# BC35_module.net
KiCad netlist of a schematic drawn in Altium Designer
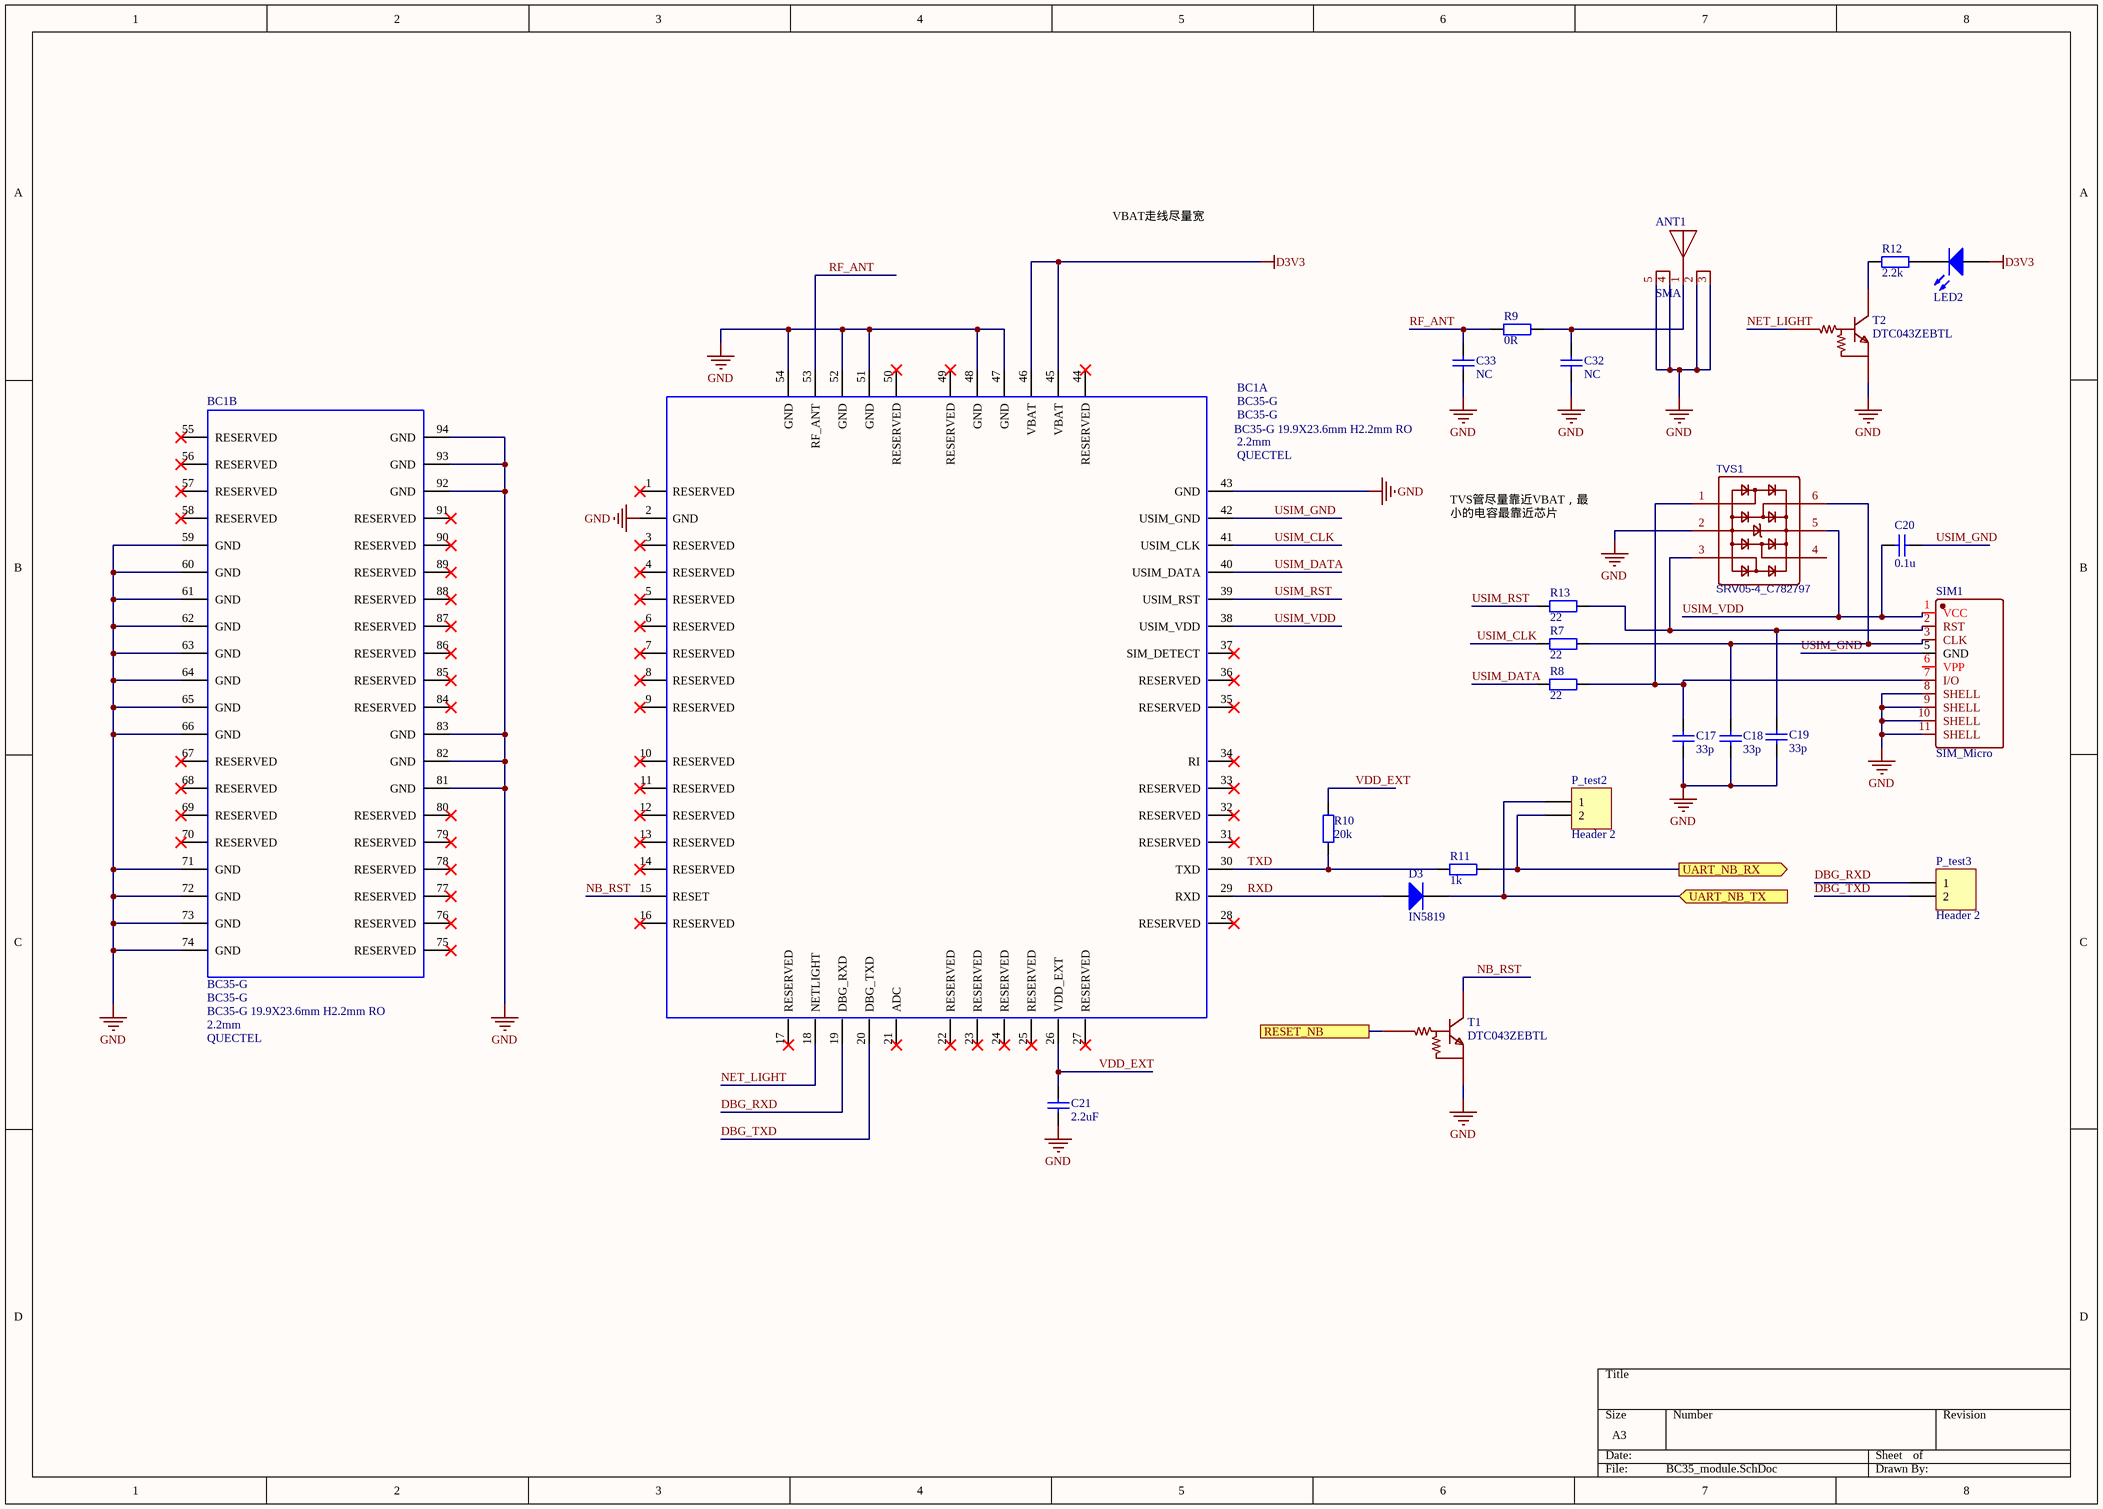
[diagram p0: BC35_module.SchDoc]

(export (version "E")
  (design (tool "Eeschema 10.0.6"))
  (components
    (comp (ref "ANT1")
      (value "SMA")
      (footprint "ANT-TH_DOSIN-806-0003")
      (libsource (lib "NBIoT") (part "SMA"))
    )
    (comp (ref "BC1")
      (value "BC35-G")
      (footprint "Quectel_BC35-G_PCB_Footprint_Protel&AD_20171010:BC35-G")
      (fields
        (field (name "ALTIUM_VALUE") "BC35-G")
        (field (name "PART DESCRIPTION") "BC35-G 19.9X23.6mm H2.2mm RO")
        (field (name "GEOMETRY.HEIGHT") "2.2mm")
        (field (name "MANUFACTURER") "QUECTEL")
      )
      (libsource (lib "Quectel_BC35-G_SCH_Part_Protel&AD_20171010") (part "BC35-G"))
    )
    (comp (ref "C17")
      (value "33p")
      (footprint "1206_C")
      (description "1206贴片电容")
      (libsource (lib "02-Miscellaneous_Devices_ZSF_Library") (part "Cap_1206"))
    )
    (comp (ref "C18")
      (value "33p")
      (footprint "1206_C")
      (description "1206贴片电容")
      (libsource (lib "02-Miscellaneous_Devices_ZSF_Library") (part "Cap_1206"))
    )
    (comp (ref "C19")
      (value "33p")
      (footprint "1206_C")
      (description "1206贴片电容")
      (libsource (lib "02-Miscellaneous_Devices_ZSF_Library") (part "Cap_1206"))
    )
    (comp (ref "C20")
      (value "0.1u")
      (footprint "1206_C")
      (description "1206贴片电容")
      (libsource (lib "02-Miscellaneous_Devices_ZSF_Library") (part "Cap_1206"))
    )
    (comp (ref "C21")
      (value "2.2uF")
      (footprint "1206_C")
      (description "1206贴片电容")
      (libsource (lib "02-Miscellaneous_Devices_ZSF_Library") (part "Cap_1206"))
    )
    (comp (ref "C32")
      (value "NC")
      (footprint "1206_C")
      (description "1206贴片电容")
      (libsource (lib "02-Miscellaneous_Devices_ZSF_Library") (part "Cap_1206"))
    )
    (comp (ref "C33")
      (value "NC")
      (footprint "1206_C")
      (description "1206贴片电容")
      (libsource (lib "02-Miscellaneous_Devices_ZSF_Library") (part "Cap_1206"))
    )
    (comp (ref "D3")
      (value "IN5819")
      (footprint "SOD-323")
      (description "二极管")
      (libsource (lib "02-Miscellaneous_Devices_ZSF_Library") (part "1N4148WS_SOD-323"))
    )
    (comp (ref "LED2")
      (value "LED Chip")
      (footprint "CLED2012-0805")
      (description "Typical Chip LED")
      (fields (field (name "PUBLISHER") "Altium Limited"))
      (libsource (lib "03-EButterflyIntegratedLibrary") (part "LED Chip"))
    )
    (comp (ref "P_test2")
      (value "Header 2")
      (footprint "XH254-2")
      (description "Header, 2-Pin")
      (fields (field (name "PUBLISHER") "Altium Limited"))
      (libsource (lib "01-Connect_IntegratedLibrary") (part "Header 2"))
    )
    (comp (ref "P_test3")
      (value "Header 2")
      (footprint "XH254-2")
      (description "Header, 2-Pin")
      (fields (field (name "PUBLISHER") "Altium Limited"))
      (libsource (lib "01-Connect_IntegratedLibrary") (part "Header 2"))
    )
    (comp (ref "R7")
      (value "22")
      (footprint "0805_R")
      (description "0805贴片电阻")
      (libsource (lib "02-Miscellaneous_Devices_ZSF_Library") (part "Res_0805"))
    )
    (comp (ref "R8")
      (value "22")
      (footprint "0805_R")
      (description "0805贴片电阻")
      (libsource (lib "02-Miscellaneous_Devices_ZSF_Library") (part "Res_0805"))
    )
    (comp (ref "R9")
      (value "0R")
      (footprint "0805_R")
      (description "0805贴片电阻")
      (libsource (lib "02-Miscellaneous_Devices_ZSF_Library") (part "Res_0805"))
    )
    (comp (ref "R10")
      (value "20k")
      (footprint "0805_R")
      (description "0805贴片电阻")
      (libsource (lib "") (part "Res_0805_1"))
    )
    (comp (ref "R11")
      (value "1k")
      (footprint "0805_R")
      (description "0805贴片电阻")
      (libsource (lib "02-Miscellaneous_Devices_ZSF_Library") (part "Res_0805"))
    )
    (comp (ref "R12")
      (value "2.2k")
      (footprint "0805_R")
      (description "0805贴片电阻")
      (libsource (lib "02-Miscellaneous_Devices_ZSF_Library") (part "Res_0805"))
    )
    (comp (ref "R13")
      (value "22")
      (footprint "0805_R")
      (description "0805贴片电阻")
      (libsource (lib "02-Miscellaneous_Devices_ZSF_Library") (part "Res_0805"))
    )
    (comp (ref "SIM1")
      (value "SIM_Micro")
      (footprint "SIM-SMD_SIM-002-P6")
      (libsource (lib "NBIoT") (part "SIM_Micro"))
    )
    (comp (ref "T1")
      (value "DTC043ZEBTL")
      (footprint "SOT-416_L1.6-W0.8-P1.00-LS1.6-BR")
      (libsource (lib "NBIoT") (part "DTC043ZEBTL"))
    )
    (comp (ref "T2")
      (value "DTC043ZEBTL")
      (footprint "SOT-416_L1.6-W0.8-P1.00-LS1.6-BR")
      (libsource (lib "NBIoT") (part "DTC043ZEBTL"))
    )
    (comp (ref "TVS1")
      (value "SRV05-4_C782797")
      (footprint "SOT-23-6_L2.9-W1.6-P0.95-LS2.8-BR")
      (fields
        (field (name "BOM_SUPPLIER PART") "C782797")
        (field (name "BOM_MANUFACTURER PART") "SRV05-4")
        (field (name "CONTRIBUTOR") "LCSC")
      )
      (libsource (lib "NBIoT") (part "SRV05-4_C782797"))
    )
  )
  (nets
    (net (code "1") (name "/DBG_RXD") (class "Default")
      (node (ref "BC1") (pin "19") (pinfunction "DBG_RXD_19") (pintype "passive"))
      (node (ref "P_test3") (pin "1") (pinfunction "1_1") (pintype "passive"))
    )
    (net (code "2") (name "/DBG_TXD") (class "Default")
      (node (ref "BC1") (pin "20") (pinfunction "DBG_TXD_20") (pintype "passive"))
      (node (ref "P_test3") (pin "2") (pinfunction "2_2") (pintype "passive"))
    )
    (net (code "3") (name "/NB_RST") (class "Default")
      (node (ref "BC1") (pin "15") (pinfunction "RESET_15") (pintype "passive"))
      (node (ref "T1") (pin "3") (pinfunction "C_3") (pintype "passive"))
    )
    (net (code "4") (name "/NET_LIGHT") (class "Default")
      (node (ref "BC1") (pin "18") (pinfunction "NETLIGHT_18") (pintype "passive"))
      (node (ref "T2") (pin "1") (pinfunction "B_1") (pintype "passive"))
    )
    (net (code "5") (name "/RESET_NB") (class "Default")
      (node (ref "T1") (pin "1") (pinfunction "B_1") (pintype "passive"))
    )
    (net (code "6") (name "/RF_ANT") (class "Default")
      (node (ref "BC1") (pin "53") (pinfunction "RF_ANT_53") (pintype "passive"))
      (node (ref "C33") (pin "2") (pinfunction "2_2") (pintype "passive"))
      (node (ref "R9") (pin "2") (pinfunction "2_2") (pintype "passive"))
    )
    (net (code "7") (name "/RXD") (class "Default")
      (node (ref "BC1") (pin "29") (pinfunction "RXD_29") (pintype "passive"))
      (node (ref "D3") (pin "1") (pinfunction "A_1") (pintype "passive"))
    )
    (net (code "8") (name "/TXD") (class "Default")
      (node (ref "BC1") (pin "30") (pinfunction "TXD_30") (pintype "passive"))
      (node (ref "R10") (pin "2") (pinfunction "2_2") (pintype "passive"))
      (node (ref "R11") (pin "2") (pinfunction "2_2") (pintype "passive"))
    )
    (net (code "9") (name "/UART_NB_RX") (class "Default")
      (node (ref "P_test2") (pin "2") (pinfunction "2_2") (pintype "passive"))
      (node (ref "R11") (pin "1") (pinfunction "1_1") (pintype "passive"))
    )
    (net (code "10") (name "/UART_NB_TX") (class "Default")
      (node (ref "D3") (pin "2") (pinfunction "K_2") (pintype "passive"))
      (node (ref "P_test2") (pin "1") (pinfunction "1_1") (pintype "passive"))
    )
    (net (code "11") (name "/USIM_CLK") (class "Default")
      (node (ref "BC1") (pin "41") (pinfunction "USIM_CLK_41") (pintype "passive"))
      (node (ref "R7") (pin "2") (pinfunction "2_2") (pintype "passive"))
    )
    (net (code "12") (name "/USIM_DATA") (class "Default")
      (node (ref "BC1") (pin "40") (pinfunction "USIM_DATA_40") (pintype "passive"))
      (node (ref "R8") (pin "2") (pinfunction "2_2") (pintype "passive"))
    )
    (net (code "13") (name "/USIM_GND") (class "Default")
      (node (ref "BC1") (pin "42") (pinfunction "USIM_GND_42") (pintype "passive"))
      (node (ref "C20") (pin "1") (pinfunction "1_1") (pintype "passive"))
      (node (ref "SIM1") (pin "5") (pinfunction "GND_5") (pintype "passive"))
    )
    (net (code "14") (name "/USIM_RST") (class "Default")
      (node (ref "BC1") (pin "39") (pinfunction "USIM_RST_39") (pintype "passive"))
      (node (ref "R13") (pin "2") (pinfunction "2_2") (pintype "passive"))
    )
    (net (code "15") (name "/USIM_VDD") (class "Default")
      (node (ref "BC1") (pin "38") (pinfunction "USIM_VDD_38") (pintype "passive"))
      (node (ref "C20") (pin "2") (pinfunction "2_2") (pintype "passive"))
      (node (ref "SIM1") (pin "1") (pinfunction "VCC_1") (pintype "passive"))
      (node (ref "TVS1") (pin "5") (pinfunction "5_5") (pintype "passive"))
    )
    (net (code "16") (name "/VDD_EXT") (class "Default")
      (node (ref "BC1") (pin "26") (pinfunction "VDD_EXT_26") (pintype "passive"))
      (node (ref "C21") (pin "2") (pinfunction "2_2") (pintype "passive"))
      (node (ref "R10") (pin "1") (pinfunction "1_1") (pintype "passive"))
    )
    (net (code "17") (name "D3V3") (class "Default")
      (node (ref "BC1") (pin "45") (pinfunction "VBAT_45") (pintype "passive"))
      (node (ref "BC1") (pin "46") (pinfunction "VBAT_46") (pintype "passive"))
      (node (ref "LED2") (pin "1") (pinfunction "A_1") (pintype "passive"))
    )
    (net (code "18") (name "GND") (class "Default")
      (node (ref "ANT1") (pin "2") (pinfunction "2_2") (pintype "passive"))
      (node (ref "ANT1") (pin "3") (pinfunction "3_3") (pintype "passive"))
      (node (ref "ANT1") (pin "4") (pinfunction "4_4") (pintype "passive"))
      (node (ref "ANT1") (pin "5") (pinfunction "5_5") (pintype "passive"))
      (node (ref "BC1") (pin "2") (pinfunction "GND_2") (pintype "passive"))
      (node (ref "BC1") (pin "43") (pinfunction "GND_43") (pintype "passive"))
      (node (ref "BC1") (pin "47") (pinfunction "GND_47") (pintype "passive"))
      (node (ref "BC1") (pin "48") (pinfunction "GND_48") (pintype "passive"))
      (node (ref "BC1") (pin "51") (pinfunction "GND_51") (pintype "passive"))
      (node (ref "BC1") (pin "52") (pinfunction "GND_52") (pintype "passive"))
      (node (ref "BC1") (pin "54") (pinfunction "GND_54") (pintype "passive"))
      (node (ref "BC1") (pin "59") (pinfunction "GND_59") (pintype "passive"))
      (node (ref "BC1") (pin "60") (pinfunction "GND_60") (pintype "passive"))
      (node (ref "BC1") (pin "61") (pinfunction "GND_61") (pintype "passive"))
      (node (ref "BC1") (pin "62") (pinfunction "GND_62") (pintype "passive"))
      (node (ref "BC1") (pin "63") (pinfunction "GND_63") (pintype "passive"))
      (node (ref "BC1") (pin "64") (pinfunction "GND_64") (pintype "passive"))
      (node (ref "BC1") (pin "65") (pinfunction "GND_65") (pintype "passive"))
      (node (ref "BC1") (pin "66") (pinfunction "GND_66") (pintype "passive"))
      (node (ref "BC1") (pin "71") (pinfunction "GND_71") (pintype "passive"))
      (node (ref "BC1") (pin "72") (pinfunction "GND_72") (pintype "passive"))
      (node (ref "BC1") (pin "73") (pinfunction "GND_73") (pintype "passive"))
      (node (ref "BC1") (pin "74") (pinfunction "GND_74") (pintype "passive"))
      (node (ref "BC1") (pin "81") (pinfunction "GND_81") (pintype "passive"))
      (node (ref "BC1") (pin "82") (pinfunction "GND_82") (pintype "passive"))
      (node (ref "BC1") (pin "83") (pinfunction "GND_83") (pintype "passive"))
      (node (ref "BC1") (pin "92") (pinfunction "GND_92") (pintype "passive"))
      (node (ref "BC1") (pin "93") (pinfunction "GND_93") (pintype "passive"))
      (node (ref "BC1") (pin "94") (pinfunction "GND_94") (pintype "passive"))
      (node (ref "C17") (pin "1") (pinfunction "1_1") (pintype "passive"))
      (node (ref "C18") (pin "1") (pinfunction "1_1") (pintype "passive"))
      (node (ref "C19") (pin "1") (pinfunction "1_1") (pintype "passive"))
      (node (ref "C21") (pin "1") (pinfunction "1_1") (pintype "passive"))
      (node (ref "C32") (pin "1") (pinfunction "1_1") (pintype "passive"))
      (node (ref "C33") (pin "1") (pinfunction "1_1") (pintype "passive"))
      (node (ref "SIM1") (pin "10") (pinfunction "SHELL_10") (pintype "passive"))
      (node (ref "SIM1") (pin "11") (pinfunction "SHELL_11") (pintype "passive"))
      (node (ref "SIM1") (pin "8") (pinfunction "SHELL_8") (pintype "passive"))
      (node (ref "SIM1") (pin "9") (pinfunction "SHELL_9") (pintype "passive"))
      (node (ref "T1") (pin "2") (pinfunction "E_2") (pintype "passive"))
      (node (ref "T2") (pin "2") (pinfunction "E_2") (pintype "passive"))
      (node (ref "TVS1") (pin "2") (pinfunction "2_2") (pintype "passive"))
    )
    (net (code "19") (name "Net-(ANT1-Pad1)") (class "Default")
      (node (ref "ANT1") (pin "1") (pinfunction "1_1") (pintype "passive"))
      (node (ref "C32") (pin "2") (pinfunction "2_2") (pintype "passive"))
      (node (ref "R9") (pin "1") (pinfunction "1_1") (pintype "passive"))
    )
    (net (code "20") (name "Net-(LED2-K)") (class "Default")
      (node (ref "LED2") (pin "2") (pinfunction "K_2") (pintype "passive"))
      (node (ref "R12") (pin "1") (pinfunction "1_1") (pintype "passive"))
    )
    (net (code "21") (name "Net-(SIM1-CLK)") (class "Default")
      (node (ref "C18") (pin "2") (pinfunction "2_2") (pintype "passive"))
      (node (ref "R7") (pin "1") (pinfunction "1_1") (pintype "passive"))
      (node (ref "SIM1") (pin "3") (pinfunction "CLK_3") (pintype "passive"))
      (node (ref "TVS1") (pin "6") (pinfunction "6_6") (pintype "passive"))
    )
    (net (code "22") (name "Net-(SIM1-I{slash}O)") (class "Default")
      (node (ref "C17") (pin "2") (pinfunction "2_2") (pintype "passive"))
      (node (ref "R8") (pin "1") (pinfunction "1_1") (pintype "passive"))
      (node (ref "SIM1") (pin "7") (pinfunction "I/O_7") (pintype "passive"))
      (node (ref "TVS1") (pin "1") (pinfunction "1_1") (pintype "passive"))
    )
    (net (code "23") (name "Net-(SIM1-RST)") (class "Default")
      (node (ref "C19") (pin "2") (pinfunction "2_2") (pintype "passive"))
      (node (ref "R13") (pin "1") (pinfunction "1_1") (pintype "passive"))
      (node (ref "SIM1") (pin "2") (pinfunction "RST_2") (pintype "passive"))
      (node (ref "TVS1") (pin "3") (pinfunction "3_3") (pintype "passive"))
    )
    (net (code "24") (name "Net-(T2-C)") (class "Default")
      (node (ref "R12") (pin "2") (pinfunction "2_2") (pintype "passive"))
      (node (ref "T2") (pin "3") (pinfunction "C_3") (pintype "passive"))
    )
    (net (code "25") (name "unconnected-(BC1A-ADC-Pad21)") (class "Default")
      (node (ref "BC1") (pin "21") (pinfunction "ADC_21") (pintype "passive+no_connect"))
    )
    (net (code "26") (name "unconnected-(BC1A-RESERVED-Pad1)") (class "Default")
      (node (ref "BC1") (pin "1") (pinfunction "RESERVED_1") (pintype "passive+no_connect"))
    )
    (net (code "27") (name "unconnected-(BC1A-RESERVED-Pad3)") (class "Default")
      (node (ref "BC1") (pin "3") (pinfunction "RESERVED_3") (pintype "passive+no_connect"))
    )
    (net (code "28") (name "unconnected-(BC1A-RESERVED-Pad4)") (class "Default")
      (node (ref "BC1") (pin "4") (pinfunction "RESERVED_4") (pintype "passive+no_connect"))
    )
    (net (code "29") (name "unconnected-(BC1A-RESERVED-Pad5)") (class "Default")
      (node (ref "BC1") (pin "5") (pinfunction "RESERVED_5") (pintype "passive+no_connect"))
    )
    (net (code "30") (name "unconnected-(BC1A-RESERVED-Pad6)") (class "Default")
      (node (ref "BC1") (pin "6") (pinfunction "RESERVED_6") (pintype "passive+no_connect"))
    )
    (net (code "31") (name "unconnected-(BC1A-RESERVED-Pad7)") (class "Default")
      (node (ref "BC1") (pin "7") (pinfunction "RESERVED_7") (pintype "passive+no_connect"))
    )
    (net (code "32") (name "unconnected-(BC1A-RESERVED-Pad8)") (class "Default")
      (node (ref "BC1") (pin "8") (pinfunction "RESERVED_8") (pintype "passive+no_connect"))
    )
    (net (code "33") (name "unconnected-(BC1A-RESERVED-Pad9)") (class "Default")
      (node (ref "BC1") (pin "9") (pinfunction "RESERVED_9") (pintype "passive+no_connect"))
    )
    (net (code "34") (name "unconnected-(BC1A-RESERVED-Pad10)") (class "Default")
      (node (ref "BC1") (pin "10") (pinfunction "RESERVED_10") (pintype "passive+no_connect"))
    )
    (net (code "35") (name "unconnected-(BC1A-RESERVED-Pad11)") (class "Default")
      (node (ref "BC1") (pin "11") (pinfunction "RESERVED_11") (pintype "passive+no_connect"))
    )
    (net (code "36") (name "unconnected-(BC1A-RESERVED-Pad12)") (class "Default")
      (node (ref "BC1") (pin "12") (pinfunction "RESERVED_12") (pintype "passive+no_connect"))
    )
    (net (code "37") (name "unconnected-(BC1A-RESERVED-Pad13)") (class "Default")
      (node (ref "BC1") (pin "13") (pinfunction "RESERVED_13") (pintype "passive+no_connect"))
    )
    (net (code "38") (name "unconnected-(BC1A-RESERVED-Pad14)") (class "Default")
      (node (ref "BC1") (pin "14") (pinfunction "RESERVED_14") (pintype "passive+no_connect"))
    )
    (net (code "39") (name "unconnected-(BC1A-RESERVED-Pad16)") (class "Default")
      (node (ref "BC1") (pin "16") (pinfunction "RESERVED_16") (pintype "passive+no_connect"))
    )
    (net (code "40") (name "unconnected-(BC1A-RESERVED-Pad17)") (class "Default")
      (node (ref "BC1") (pin "17") (pinfunction "RESERVED_17") (pintype "passive+no_connect"))
    )
    (net (code "41") (name "unconnected-(BC1A-RESERVED-Pad22)") (class "Default")
      (node (ref "BC1") (pin "22") (pinfunction "RESERVED_22") (pintype "passive+no_connect"))
    )
    (net (code "42") (name "unconnected-(BC1A-RESERVED-Pad23)") (class "Default")
      (node (ref "BC1") (pin "23") (pinfunction "RESERVED_23") (pintype "passive+no_connect"))
    )
    (net (code "43") (name "unconnected-(BC1A-RESERVED-Pad24)") (class "Default")
      (node (ref "BC1") (pin "24") (pinfunction "RESERVED_24") (pintype "passive+no_connect"))
    )
    (net (code "44") (name "unconnected-(BC1A-RESERVED-Pad25)") (class "Default")
      (node (ref "BC1") (pin "25") (pinfunction "RESERVED_25") (pintype "passive+no_connect"))
    )
    (net (code "45") (name "unconnected-(BC1A-RESERVED-Pad27)") (class "Default")
      (node (ref "BC1") (pin "27") (pinfunction "RESERVED_27") (pintype "passive+no_connect"))
    )
    (net (code "46") (name "unconnected-(BC1A-RESERVED-Pad28)") (class "Default")
      (node (ref "BC1") (pin "28") (pinfunction "RESERVED_28") (pintype "passive+no_connect"))
    )
    (net (code "47") (name "unconnected-(BC1A-RESERVED-Pad31)") (class "Default")
      (node (ref "BC1") (pin "31") (pinfunction "RESERVED_31") (pintype "passive+no_connect"))
    )
    (net (code "48") (name "unconnected-(BC1A-RESERVED-Pad32)") (class "Default")
      (node (ref "BC1") (pin "32") (pinfunction "RESERVED_32") (pintype "passive+no_connect"))
    )
    (net (code "49") (name "unconnected-(BC1A-RESERVED-Pad33)") (class "Default")
      (node (ref "BC1") (pin "33") (pinfunction "RESERVED_33") (pintype "passive+no_connect"))
    )
    (net (code "50") (name "unconnected-(BC1A-RESERVED-Pad35)") (class "Default")
      (node (ref "BC1") (pin "35") (pinfunction "RESERVED_35") (pintype "passive+no_connect"))
    )
    (net (code "51") (name "unconnected-(BC1A-RESERVED-Pad36)") (class "Default")
      (node (ref "BC1") (pin "36") (pinfunction "RESERVED_36") (pintype "passive+no_connect"))
    )
    (net (code "52") (name "unconnected-(BC1A-RESERVED-Pad44)") (class "Default")
      (node (ref "BC1") (pin "44") (pinfunction "RESERVED_44") (pintype "passive+no_connect"))
    )
    (net (code "53") (name "unconnected-(BC1A-RESERVED-Pad49)") (class "Default")
      (node (ref "BC1") (pin "49") (pinfunction "RESERVED_49") (pintype "passive+no_connect"))
    )
    (net (code "54") (name "unconnected-(BC1A-RESERVED-Pad50)") (class "Default")
      (node (ref "BC1") (pin "50") (pinfunction "RESERVED_50") (pintype "passive+no_connect"))
    )
    (net (code "55") (name "unconnected-(BC1A-RI-Pad34)") (class "Default")
      (node (ref "BC1") (pin "34") (pinfunction "RI_34") (pintype "passive+no_connect"))
    )
    (net (code "56") (name "unconnected-(BC1A-SIM_DETECT-Pad37)") (class "Default")
      (node (ref "BC1") (pin "37") (pinfunction "SIM_DETECT_37") (pintype "passive+no_connect"))
    )
    (net (code "57") (name "unconnected-(BC1B-RESERVED-Pad55)") (class "Default")
      (node (ref "BC1") (pin "55") (pinfunction "RESERVED_55") (pintype "passive+no_connect"))
    )
    (net (code "58") (name "unconnected-(BC1B-RESERVED-Pad56)") (class "Default")
      (node (ref "BC1") (pin "56") (pinfunction "RESERVED_56") (pintype "passive+no_connect"))
    )
    (net (code "59") (name "unconnected-(BC1B-RESERVED-Pad57)") (class "Default")
      (node (ref "BC1") (pin "57") (pinfunction "RESERVED_57") (pintype "passive+no_connect"))
    )
    (net (code "60") (name "unconnected-(BC1B-RESERVED-Pad58)") (class "Default")
      (node (ref "BC1") (pin "58") (pinfunction "RESERVED_58") (pintype "passive+no_connect"))
    )
    (net (code "61") (name "unconnected-(BC1B-RESERVED-Pad67)") (class "Default")
      (node (ref "BC1") (pin "67") (pinfunction "RESERVED_67") (pintype "passive+no_connect"))
    )
    (net (code "62") (name "unconnected-(BC1B-RESERVED-Pad68)") (class "Default")
      (node (ref "BC1") (pin "68") (pinfunction "RESERVED_68") (pintype "passive+no_connect"))
    )
    (net (code "63") (name "unconnected-(BC1B-RESERVED-Pad69)") (class "Default")
      (node (ref "BC1") (pin "69") (pinfunction "RESERVED_69") (pintype "passive+no_connect"))
    )
    (net (code "64") (name "unconnected-(BC1B-RESERVED-Pad70)") (class "Default")
      (node (ref "BC1") (pin "70") (pinfunction "RESERVED_70") (pintype "passive+no_connect"))
    )
    (net (code "65") (name "unconnected-(BC1B-RESERVED-Pad75)") (class "Default")
      (node (ref "BC1") (pin "75") (pinfunction "RESERVED_75") (pintype "passive+no_connect"))
    )
    (net (code "66") (name "unconnected-(BC1B-RESERVED-Pad76)") (class "Default")
      (node (ref "BC1") (pin "76") (pinfunction "RESERVED_76") (pintype "passive+no_connect"))
    )
    (net (code "67") (name "unconnected-(BC1B-RESERVED-Pad77)") (class "Default")
      (node (ref "BC1") (pin "77") (pinfunction "RESERVED_77") (pintype "passive+no_connect"))
    )
    (net (code "68") (name "unconnected-(BC1B-RESERVED-Pad78)") (class "Default")
      (node (ref "BC1") (pin "78") (pinfunction "RESERVED_78") (pintype "passive+no_connect"))
    )
    (net (code "69") (name "unconnected-(BC1B-RESERVED-Pad79)") (class "Default")
      (node (ref "BC1") (pin "79") (pinfunction "RESERVED_79") (pintype "passive+no_connect"))
    )
    (net (code "70") (name "unconnected-(BC1B-RESERVED-Pad80)") (class "Default")
      (node (ref "BC1") (pin "80") (pinfunction "RESERVED_80") (pintype "passive+no_connect"))
    )
    (net (code "71") (name "unconnected-(BC1B-RESERVED-Pad84)") (class "Default")
      (node (ref "BC1") (pin "84") (pinfunction "RESERVED_84") (pintype "passive+no_connect"))
    )
    (net (code "72") (name "unconnected-(BC1B-RESERVED-Pad85)") (class "Default")
      (node (ref "BC1") (pin "85") (pinfunction "RESERVED_85") (pintype "passive+no_connect"))
    )
    (net (code "73") (name "unconnected-(BC1B-RESERVED-Pad86)") (class "Default")
      (node (ref "BC1") (pin "86") (pinfunction "RESERVED_86") (pintype "passive+no_connect"))
    )
    (net (code "74") (name "unconnected-(BC1B-RESERVED-Pad87)") (class "Default")
      (node (ref "BC1") (pin "87") (pinfunction "RESERVED_87") (pintype "passive+no_connect"))
    )
    (net (code "75") (name "unconnected-(BC1B-RESERVED-Pad88)") (class "Default")
      (node (ref "BC1") (pin "88") (pinfunction "RESERVED_88") (pintype "passive+no_connect"))
    )
    (net (code "76") (name "unconnected-(BC1B-RESERVED-Pad89)") (class "Default")
      (node (ref "BC1") (pin "89") (pinfunction "RESERVED_89") (pintype "passive+no_connect"))
    )
    (net (code "77") (name "unconnected-(BC1B-RESERVED-Pad90)") (class "Default")
      (node (ref "BC1") (pin "90") (pinfunction "RESERVED_90") (pintype "passive+no_connect"))
    )
    (net (code "78") (name "unconnected-(BC1B-RESERVED-Pad91)") (class "Default")
      (node (ref "BC1") (pin "91") (pinfunction "RESERVED_91") (pintype "passive+no_connect"))
    )
    (net (code "79") (name "unconnected-(SIM1-VPP-Pad6)") (class "Default")
      (node (ref "SIM1") (pin "6") (pinfunction "VPP_6") (pintype "passive"))
    )
    (net (code "80") (name "unconnected-(TVS1-Pad4)") (class "Default")
      (node (ref "TVS1") (pin "4") (pinfunction "4_4") (pintype "passive"))
    )
  )
)
